# Trabajo3.net
KiCad netlist of a schematic drawn in EAGLE
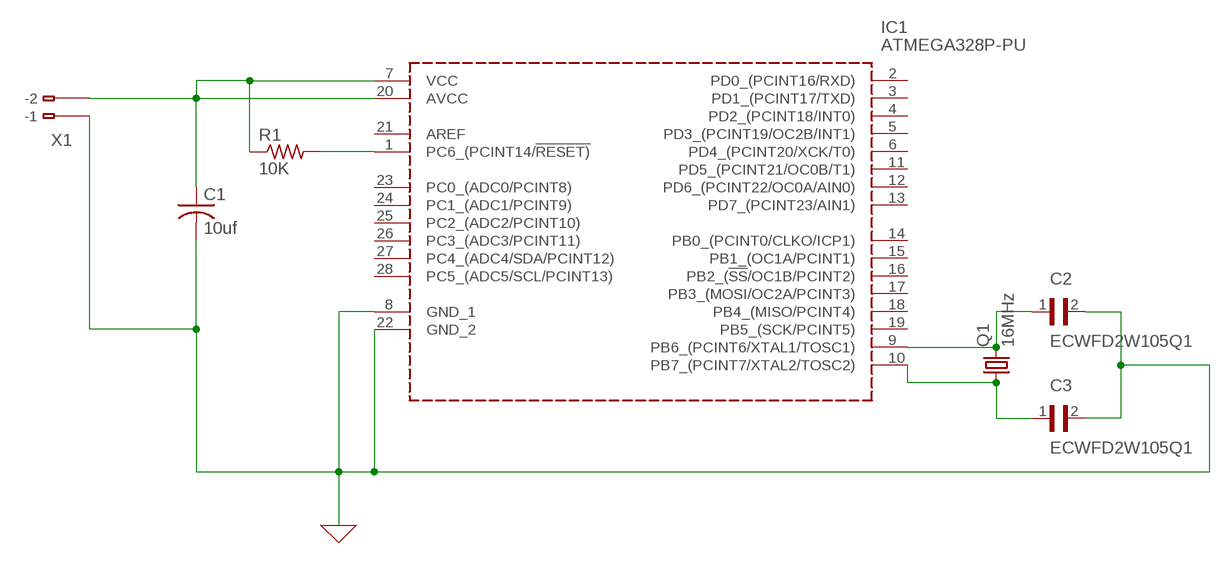
[diagram p0: schematic, sheet 1]

(export (version "E")
  (design (tool "Eeschema 10.0.6"))
  (components
    (comp (ref "C1")
      (value "10uf")
      (footprint "eagle-import:C025-024X044")
      (fields (field (name "POPULARITY") "10Uf"))
      (libsource (lib "eagle-import") (part "C-US025-024X044"))
    )
    (comp (ref "C2")
      (value "ECWFD2W105Q1")
      (footprint "eagle-import:CAPRR1000W60L1260T920H1390")
      (fields (field (name "MF") "Panasonic"))
      (libsource (lib "eagle-import") (part "ECWFD2W105Q1"))
    )
    (comp (ref "C3")
      (value "ECWFD2W105Q1")
      (footprint "eagle-import:CAPRR1000W60L1260T920H1390")
      (fields (field (name "MF") "Panasonic"))
      (libsource (lib "eagle-import") (part "ECWFD2W105Q1"))
    )
    (comp (ref "IC1")
      (value "ATMEGA328P-PU")
      (footprint "eagle-import:DIP794W53P254L3467H457Q28N")
      (fields (field (name "MF") "Microchip Technology") (field (name "MP") "ATMEGA328PPU"))
      (libsource (lib "eagle-import") (part "ATMEGA328P-PU"))
    )
    (comp (ref "Q1")
      (value "16MHz")
      (footprint "eagle-import:HC33U-V")
      (libsource (lib "eagle-import") (part "CRYSTALHC33U-V"))
    )
    (comp (ref "R1")
      (value "10K")
      (footprint "eagle-import:0204V")
      (fields (field (name "POPULARITY") "10k"))
      (libsource (lib "eagle-import") (part "R-US_0204/2V"))
    )
    (comp (ref "X1")
      (value "233-102")
      (footprint "eagle-import:233-102")
      (libsource (lib "eagle-import") (part "233-102"))
    )
  )
  (nets
    (net (code "1") (name "GND") (class "Default")
      (node (ref "C1") (pin "2") (pinfunction "2_2") (pintype "passive"))
      (node (ref "C2") (pin "2") (pinfunction "2_2") (pintype "passive"))
      (node (ref "C3") (pin "2") (pinfunction "2_2") (pintype "passive"))
      (node (ref "IC1") (pin "22") (pinfunction "GND_2_22") (pintype "bidirectional"))
      (node (ref "IC1") (pin "8") (pinfunction "GND_1_8") (pintype "bidirectional"))
      (node (ref "X1") (pin "B1") (pinfunction "B-1_B1") (pintype "passive"))
    )
    (net (code "2") (name "Net-(IC1-AVCC)") (class "Default")
      (node (ref "C1") (pin "1") (pinfunction "1_1") (pintype "passive"))
      (node (ref "IC1") (pin "20") (pinfunction "AVCC_20") (pintype "bidirectional"))
      (node (ref "IC1") (pin "7") (pinfunction "VCC_7") (pintype "bidirectional"))
      (node (ref "R1") (pin "1") (pinfunction "1_1") (pintype "passive"))
      (node (ref "X1") (pin "B2") (pinfunction "B-2_B2") (pintype "passive"))
    )
    (net (code "3") (name "Net-(IC1-PB6_(PCINT6{slash}XTAL1{slash}TOSC1))") (class "Default")
      (node (ref "C2") (pin "1") (pinfunction "1_1") (pintype "passive"))
      (node (ref "IC1") (pin "9") (pinfunction "PB6_(PCINT6/XTAL1/TOSC1)_9") (pintype "bidirectional"))
      (node (ref "Q1") (pin "2") (pinfunction "2_2") (pintype "passive"))
    )
    (net (code "4") (name "Net-(IC1-PB7_(PCINT7{slash}XTAL2{slash}TOSC2))") (class "Default")
      (node (ref "C3") (pin "1") (pinfunction "1_1") (pintype "passive"))
      (node (ref "IC1") (pin "10") (pinfunction "PB7_(PCINT7/XTAL2/TOSC2)_10") (pintype "bidirectional"))
      (node (ref "Q1") (pin "1") (pinfunction "1_1") (pintype "passive"))
    )
    (net (code "5") (name "Net-(IC1-PC6_(PCINT14{slash}~{RESET}))") (class "Default")
      (node (ref "IC1") (pin "1") (pinfunction "PC6_(PCINT14/~{RESET})_1") (pintype "bidirectional"))
      (node (ref "R1") (pin "2") (pinfunction "2_2") (pintype "passive"))
    )
    (net (code "6") (name "unconnected-(IC1-AREF-Pad21)") (class "Default")
      (node (ref "IC1") (pin "21") (pinfunction "AREF_21") (pintype "bidirectional"))
    )
    (net (code "7") (name "unconnected-(IC1-PB0_(PCINT0{slash}CLKO{slash}ICP1)-Pad14)") (class "Default")
      (node (ref "IC1") (pin "14") (pinfunction "PB0_(PCINT0/CLKO/ICP1)_14") (pintype "bidirectional"))
    )
    (net (code "8") (name "unconnected-(IC1-PB1_(OC1A{slash}PCINT1)-Pad15)") (class "Default")
      (node (ref "IC1") (pin "15") (pinfunction "PB1_(OC1A/PCINT1)_15") (pintype "bidirectional"))
    )
    (net (code "9") (name "unconnected-(IC1-PB2_(~{SS}{slash}OC1B{slash}PCINT2)-Pad16)") (class "Default")
      (node (ref "IC1") (pin "16") (pinfunction "PB2_(~{SS}/OC1B/PCINT2)_16") (pintype "bidirectional"))
    )
    (net (code "10") (name "unconnected-(IC1-PB3_(MOSI{slash}OC2A{slash}PCINT3)-Pad17)") (class "Default")
      (node (ref "IC1") (pin "17") (pinfunction "PB3_(MOSI/OC2A/PCINT3)_17") (pintype "bidirectional"))
    )
    (net (code "11") (name "unconnected-(IC1-PB4_(MISO{slash}PCINT4)-Pad18)") (class "Default")
      (node (ref "IC1") (pin "18") (pinfunction "PB4_(MISO/PCINT4)_18") (pintype "bidirectional"))
    )
    (net (code "12") (name "unconnected-(IC1-PB5_(SCK{slash}PCINT5)-Pad19)") (class "Default")
      (node (ref "IC1") (pin "19") (pinfunction "PB5_(SCK/PCINT5)_19") (pintype "bidirectional"))
    )
    (net (code "13") (name "unconnected-(IC1-PC0_(ADC0{slash}PCINT8)-Pad23)") (class "Default")
      (node (ref "IC1") (pin "23") (pinfunction "PC0_(ADC0/PCINT8)_23") (pintype "bidirectional"))
    )
    (net (code "14") (name "unconnected-(IC1-PC1_(ADC1{slash}PCINT9)-Pad24)") (class "Default")
      (node (ref "IC1") (pin "24") (pinfunction "PC1_(ADC1/PCINT9)_24") (pintype "bidirectional"))
    )
    (net (code "15") (name "unconnected-(IC1-PC2_(ADC2{slash}PCINT10)-Pad25)") (class "Default")
      (node (ref "IC1") (pin "25") (pinfunction "PC2_(ADC2/PCINT10)_25") (pintype "bidirectional"))
    )
    (net (code "16") (name "unconnected-(IC1-PC3_(ADC3{slash}PCINT11)-Pad26)") (class "Default")
      (node (ref "IC1") (pin "26") (pinfunction "PC3_(ADC3/PCINT11)_26") (pintype "bidirectional"))
    )
    (net (code "17") (name "unconnected-(IC1-PC4_(ADC4{slash}SDA{slash}PCINT12)-Pad27)") (class "Default")
      (node (ref "IC1") (pin "27") (pinfunction "PC4_(ADC4/SDA/PCINT12)_27") (pintype "bidirectional"))
    )
    (net (code "18") (name "unconnected-(IC1-PC5_(ADC5{slash}SCL{slash}PCINT13)-Pad28)") (class "Default")
      (node (ref "IC1") (pin "28") (pinfunction "PC5_(ADC5/SCL/PCINT13)_28") (pintype "bidirectional"))
    )
    (net (code "19") (name "unconnected-(IC1-PD0_(PCINT16{slash}RXD)-Pad2)") (class "Default")
      (node (ref "IC1") (pin "2") (pinfunction "PD0_(PCINT16/RXD)_2") (pintype "bidirectional"))
    )
    (net (code "20") (name "unconnected-(IC1-PD1_(PCINT17{slash}TXD)-Pad3)") (class "Default")
      (node (ref "IC1") (pin "3") (pinfunction "PD1_(PCINT17/TXD)_3") (pintype "bidirectional"))
    )
    (net (code "21") (name "unconnected-(IC1-PD2_(PCINT18{slash}INT0)-Pad4)") (class "Default")
      (node (ref "IC1") (pin "4") (pinfunction "PD2_(PCINT18/INT0)_4") (pintype "bidirectional"))
    )
    (net (code "22") (name "unconnected-(IC1-PD3_(PCINT19{slash}OC2B{slash}INT1)-Pad5)") (class "Default")
      (node (ref "IC1") (pin "5") (pinfunction "PD3_(PCINT19/OC2B/INT1)_5") (pintype "bidirectional"))
    )
    (net (code "23") (name "unconnected-(IC1-PD4_(PCINT20{slash}XCK{slash}T0)-Pad6)") (class "Default")
      (node (ref "IC1") (pin "6") (pinfunction "PD4_(PCINT20/XCK/T0)_6") (pintype "bidirectional"))
    )
    (net (code "24") (name "unconnected-(IC1-PD5_(PCINT21{slash}OC0B{slash}T1)-Pad11)") (class "Default")
      (node (ref "IC1") (pin "11") (pinfunction "PD5_(PCINT21/OC0B/T1)_11") (pintype "bidirectional"))
    )
    (net (code "25") (name "unconnected-(IC1-PD6_(PCINT22{slash}OC0A{slash}AIN0)-Pad12)") (class "Default")
      (node (ref "IC1") (pin "12") (pinfunction "PD6_(PCINT22/OC0A/AIN0)_12") (pintype "bidirectional"))
    )
    (net (code "26") (name "unconnected-(IC1-PD7_(PCINT23{slash}AIN1)-Pad13)") (class "Default")
      (node (ref "IC1") (pin "13") (pinfunction "PD7_(PCINT23/AIN1)_13") (pintype "bidirectional"))
    )
    (net (code "27") (name "unconnected-(X1--1-PadA1)") (class "Default")
      (node (ref "X1") (pin "A1") (pinfunction "-1_A1") (pintype "passive"))
    )
    (net (code "28") (name "unconnected-(X1--2-PadA2)") (class "Default")
      (node (ref "X1") (pin "A2") (pinfunction "-2_A2") (pintype "passive"))
    )
  )
)
